# CareLite_1_21.net
KiCad netlist of a schematic drawn in Altium Designer
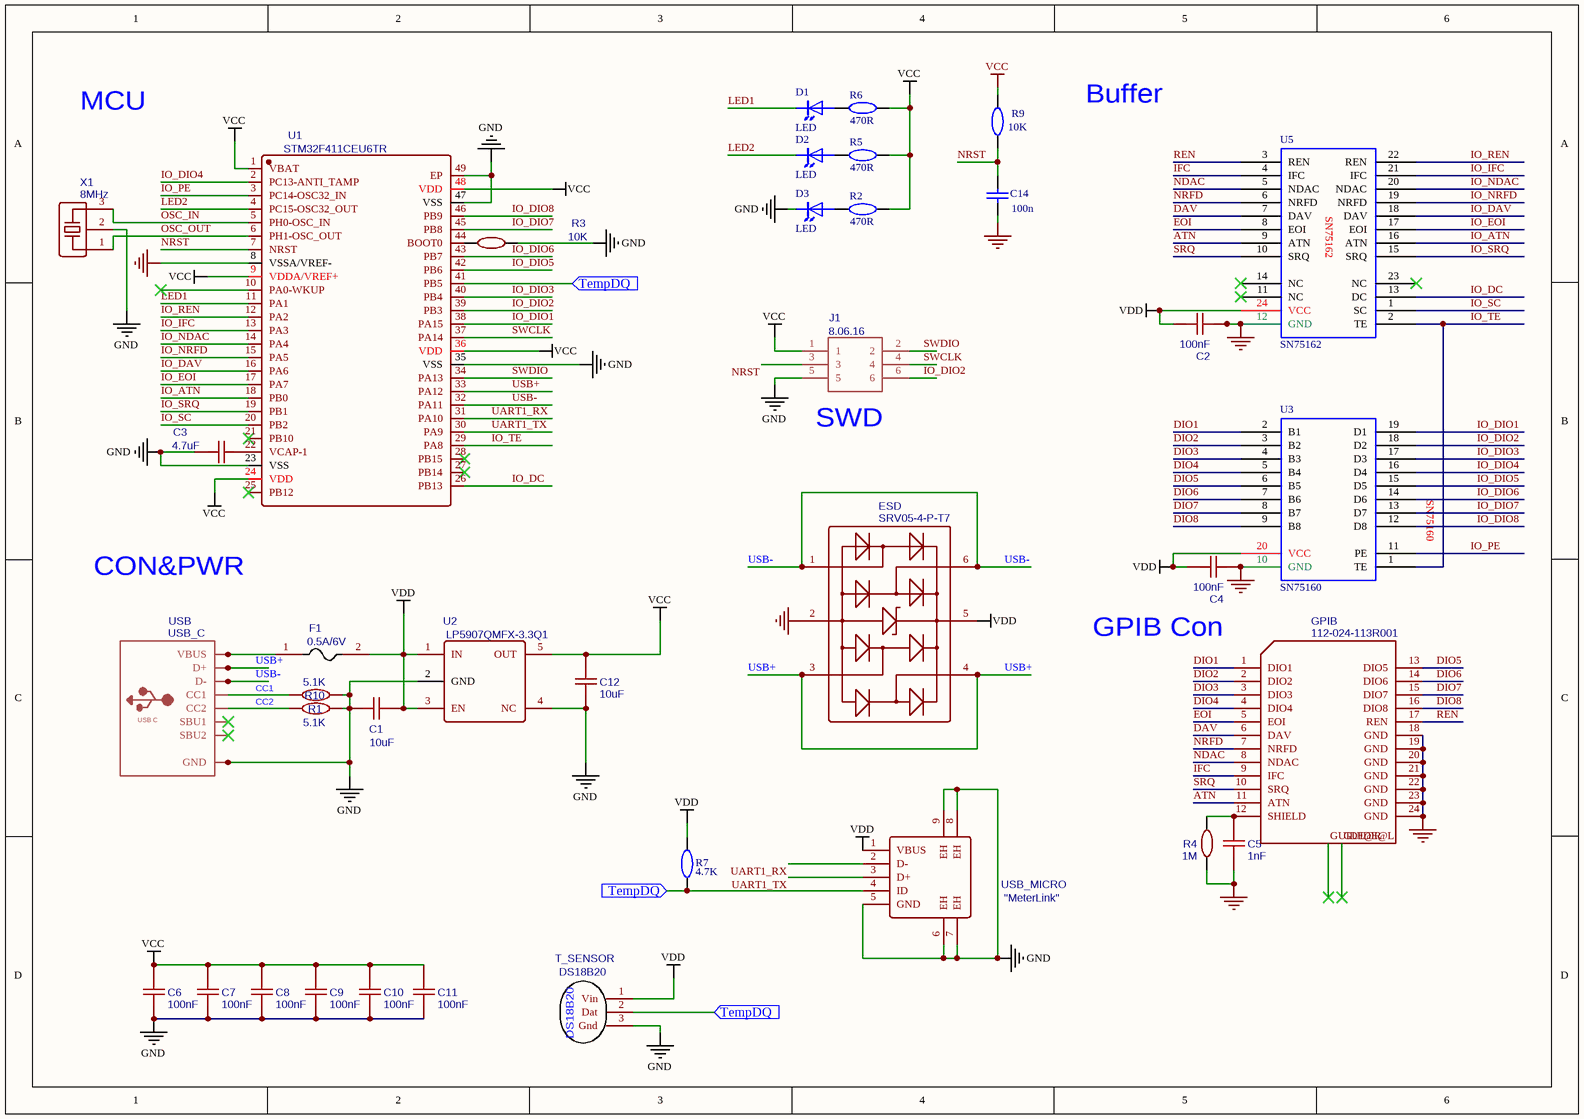
[diagram p0: CareLite 1.21.schdoc]

(export (version "E")
  (design (tool "Eeschema 10.0.6"))
  (components
    (comp (ref "C1")
      (value "10uF")
      (footprint "C0603")
      (fields
        (field (name "MANUFACTURER") "TAIYO YUDEN")
        (field (name "MANUFACTURER PART") "LMK107BJ106MALTD")
      )
      (libsource (lib "altium-import") (part "root_0_10uF_"))
    )
    (comp (ref "C2")
      (value "100nF")
      (footprint "C0603")
      (fields (field (name "MANUFACTURER") "YAGEO") (field (name "MANUFACTURER PART") "CC0402KRX7R7BB104"))
      (libsource (lib "altium-import") (part "root_2_100nF_"))
    )
    (comp (ref "C3")
      (value "4.7uF")
      (footprint "C0603")
      (fields
        (field (name "MANUFACTURER") "Huaxin S&T")
        (field (name "MANUFACTURER PART") "0603X475K160CT")
        (field (name "CONTRIBUTOR") "LCSC")
      )
      (libsource (lib "altium-import") (part "root_3_4.7uF_"))
    )
    (comp (ref "C4")
      (value "100nF")
      (footprint "C0603")
      (fields (field (name "MANUFACTURER") "YAGEO") (field (name "MANUFACTURER PART") "CC0402KRX7R7BB104"))
      (libsource (lib "altium-import") (part "root_2_100nF_"))
    )
    (comp (ref "C5")
      (value "1nF")
      (footprint "C0603")
      (fields
        (field (name "MANUFACTURER") "YAGEO")
        (field (name "MANUFACTURER PART") "CC0603KRX7RABB102")
        (field (name "CONTRIBUTOR") "LCSC")
      )
      (libsource (lib "altium-import") (part "root_0_1nF_"))
    )
    (comp (ref "C6")
      (value "100nF")
      (footprint "C0603")
      (fields (field (name "MANUFACTURER") "YAGEO") (field (name "MANUFACTURER PART") "CC0402KRX7R7BB104"))
      (libsource (lib "altium-import") (part "root_1_100nF_"))
    )
    (comp (ref "C7")
      (value "100nF")
      (footprint "C0603")
      (fields (field (name "MANUFACTURER") "YAGEO") (field (name "MANUFACTURER PART") "CC0402KRX7R7BB104"))
      (libsource (lib "altium-import") (part "root_1_100nF_"))
    )
    (comp (ref "C8")
      (value "100nF")
      (footprint "C0603")
      (fields (field (name "MANUFACTURER") "YAGEO") (field (name "MANUFACTURER PART") "CC0402KRX7R7BB104"))
      (libsource (lib "altium-import") (part "root_1_100nF_"))
    )
    (comp (ref "C9")
      (value "100nF")
      (footprint "C0603")
      (fields (field (name "MANUFACTURER") "YAGEO") (field (name "MANUFACTURER PART") "CC0402KRX7R7BB104"))
      (libsource (lib "altium-import") (part "root_1_100nF_"))
    )
    (comp (ref "C10")
      (value "100nF")
      (footprint "C0603")
      (fields (field (name "MANUFACTURER") "YAGEO") (field (name "MANUFACTURER PART") "CC0402KRX7R7BB104"))
      (libsource (lib "altium-import") (part "root_1_100nF_"))
    )
    (comp (ref "C11")
      (value "100nF")
      (footprint "C0603")
      (fields (field (name "MANUFACTURER") "YAGEO") (field (name "MANUFACTURER PART") "CC0402KRX7R7BB104"))
      (libsource (lib "altium-import") (part "root_1_100nF_"))
    )
    (comp (ref "C12")
      (value "10uF")
      (footprint "C0603")
      (fields
        (field (name "MANUFACTURER") "TAIYO YUDEN")
        (field (name "MANUFACTURER PART") "LMK107BJ106MALTD")
      )
      (libsource (lib "altium-import") (part "root_1_10uF_"))
    )
    (comp (ref "C14")
      (value "100n")
      (footprint "C0603")
      (fields (field (name "PUBLISHER") "Altium Limited"))
      (libsource (lib "altium-import") (part "root_1_100n_"))
    )
    (comp (ref "D1")
      (value "LED")
      (footprint "LED0603-FD")
      (libsource (lib "altium-import") (part "root_2_LED_"))
    )
    (comp (ref "D2")
      (value "LED")
      (footprint "LED0603-FD")
      (libsource (lib "altium-import") (part "root_2_LED_"))
    )
    (comp (ref "D3")
      (value "LED")
      (footprint "LED0603-FD")
      (libsource (lib "altium-import") (part "root_2_LED_"))
    )
    (comp (ref "ESD")
      (value "SRV05-4-P-T7")
      (footprint "SOT-23-6_L2.9-W1.6-P0.95-LS2.8-BL")
      (fields (field (name "MANUFACTURER") "PROTEK"))
      (libsource (lib "altium-import") (part "root_0_SRV05-4-P-T7_"))
    )
    (comp (ref "F1")
      (value "0.5A/6V")
      (footprint "0805_L_JX")
      (libsource (lib "altium-import") (part "root_0_0.5A/6V_"))
    )
    (comp (ref "GPIB")
      (value "112-024-113R001")
      (footprint "IEEE-488 SOCKET, 24PIN, RIGHT ANGLE, MALE, 112-024-113R001, FUY57109")
      (fields (field (name "MANUFACTURER") "norcomp") (field (name "CONTRIBUTOR") "misslee"))
      (libsource (lib "altium-import") (part "root_0_112-024-113R001_"))
    )
    (comp (ref "J1")
      (value "8.06.16")
      (footprint "80616-S")
      (fields (field (name "CONTRIBUTOR") "misslee"))
      (libsource (lib "altium-import") (part "root_0_8.06.16_"))
    )
    (comp (ref "R1")
      (value "5.1K")
      (footprint "R0603")
      (fields
        (field (name "MANUFACTURER") "Guangdong Fenghua Advanced Tech")
        (field (name "MANUFACTURER PART") "RS-03K5101FT")
        (field (name "CONTRIBUTOR") "LCSC")
      )
      (libsource (lib "altium-import") (part "root_0_5.1K_"))
    )
    (comp (ref "R2")
      (value "470R")
      (footprint "R0603")
      (fields (field (name "PUBLISHER") "Altium Limited"))
      (libsource (lib "altium-import") (part "root_2_470R_"))
    )
    (comp (ref "R3")
      (value "10K")
      (footprint "R0603")
      (fields (field (name "MANUFACTURER") "YAGEO") (field (name "MANUFACTURER PART") "RC0402FR-0710KL"))
      (libsource (lib "altium-import") (part "root_0_10K_"))
    )
    (comp (ref "R4")
      (value "1M")
      (footprint "R0603")
      (fields (field (name "MANUFACTURER") "YAGEO") (field (name "MANUFACTURER PART") "RC0603JR-071ML"))
      (libsource (lib "altium-import") (part "root_3_1M_"))
    )
    (comp (ref "R5")
      (value "470R")
      (footprint "R0603")
      (fields (field (name "PUBLISHER") "Altium Limited"))
      (libsource (lib "altium-import") (part "root_2_470R_"))
    )
    (comp (ref "R6")
      (value "470R")
      (footprint "R0603")
      (fields (field (name "PUBLISHER") "Altium Limited"))
      (libsource (lib "altium-import") (part "root_2_470R_"))
    )
    (comp (ref "R7")
      (value "4.7K")
      (footprint "R0603")
      (fields (field (name "PUBLISHER") "Altium Limited"))
      (libsource (lib "altium-import") (part "root_3_4.7K_"))
    )
    (comp (ref "R9")
      (value "10K")
      (footprint "R0603")
      (fields (field (name "PUBLISHER") "Altium Limited"))
      (libsource (lib "altium-import") (part "root_1_10K_"))
    )
    (comp (ref "R10")
      (value "5.1K")
      (footprint "R0603")
      (fields
        (field (name "MANUFACTURER") "Guangdong Fenghua Advanced Tech")
        (field (name "MANUFACTURER PART") "RS-03K5101FT")
        (field (name "CONTRIBUTOR") "LCSC")
      )
      (libsource (lib "altium-import") (part "root_0_5.1K_"))
    )
    (comp (ref "T_SENSOR")
      (value "DS18B20")
      (footprint "DS18B20")
      (fields (field (name "CONTRIBUTOR") "aleja_claros"))
      (libsource (lib "altium-import") (part "root_0_DS18B20_"))
    )
    (comp (ref "U1")
      (value "STM32F411CEU6TR")
      (footprint "QFN-48_L7.0-W7.0-P0.50-BL-EP5.1")
      (fields
        (field (name "MANUFACTURER") "STMicroelectronics")
        (field (name "MANUFACTURER PART") "STM32F411CCU6TR")
        (field (name "CONTRIBUTOR") "LCSC")
      )
      (libsource (lib "altium-import") (part "root_0_STM32F411CEU6TR_"))
    )
    (comp (ref "U2")
      (value "LP5907QMFX-3.3Q1")
      (footprint "SOT-23-5_L3.0-W1.7-P0.95-LS2.8-BR")
      (fields (field (name "MANUFACTURER") "TI") (field (name "CONTRIBUTOR") "LCSC"))
      (libsource (lib "altium-import") (part "root_0_LP5907QMFX-3.3Q1_"))
    )
    (comp (ref "U3")
      (value "SN75160")
      (footprint "SOIC127P1030-20AM")
      (libsource (lib "altium-import") (part "root_0_SN75160_"))
    )
    (comp (ref "U5")
      (value "SN75162")
      (footprint "SOIC127P1030-24AM")
      (libsource (lib "altium-import") (part "root_0_SN75162_"))
    )
    (comp (ref "USB")
      (value "USB_C")
      (footprint "USB_C_CUSB31-CFM2AX-01-Y")
      (fields (field (name "CONTRIBUTOR") "misslee"))
      (libsource (lib "altium-import") (part "root_0_USB_C_"))
    )
    (comp (ref "USB_MICRO")
      (value "\"MeterLink\"")
      (footprint "MIRCO-USB-SMD_U-D-M7DS-G-2")
      (fields
        (field (name "MANUFACTURER") "XKB Connectivity(中国星坤)")
        (field (name "MANUFACTURER PART") "U-D-M7DS-G-2")
        (field (name "CONTRIBUTOR") "LCSC")
      )
      (libsource (lib "altium-import") (part "root_0_{dblquote}MeterLink{dblquote}_"))
    )
    (comp (ref "X1")
      (value "8MHz")
      (footprint "OSC-SMD_3P-L3.2-W1.3-P1.2-L")
      (fields (field (name "MANUFACTURER PART") "CSTCE8M00G52-R0") (field (name "MANUFACTURER") "MuRata"))
      (libsource (lib "altium-import") (part "root_1_8MHz_"))
    )
  )
  (nets
    (net (code "1") (name "/ATN") (class "Default")
      (node (ref "GPIB") (pin "11") (pinfunction "ATN_11") (pintype "passive"))
      (node (ref "U5") (pin "9") (pinfunction "ATN_9") (pintype "passive"))
    )
    (net (code "2") (name "/CC1") (class "Default")
      (node (ref "R10") (pin "1") (pinfunction "1_1") (pintype "passive"))
      (node (ref "USB") (pin "A5") (pinfunction "CC1_A5") (pintype "passive"))
    )
    (net (code "3") (name "/CC2") (class "Default")
      (node (ref "R1") (pin "1") (pinfunction "1_1") (pintype "passive"))
      (node (ref "USB") (pin "B5") (pinfunction "CC2_B5") (pintype "passive"))
    )
    (net (code "4") (name "/DAV") (class "Default")
      (node (ref "GPIB") (pin "6") (pinfunction "DAV_6") (pintype "passive"))
      (node (ref "U5") (pin "7") (pinfunction "DAV_7") (pintype "passive"))
    )
    (net (code "5") (name "/DIO1") (class "Default")
      (node (ref "GPIB") (pin "1") (pinfunction "DIO1_1") (pintype "passive"))
      (node (ref "U3") (pin "2") (pinfunction "B1_2") (pintype "passive"))
    )
    (net (code "6") (name "/DIO2") (class "Default")
      (node (ref "GPIB") (pin "2") (pinfunction "DIO2_2") (pintype "passive"))
      (node (ref "U3") (pin "3") (pinfunction "B2_3") (pintype "passive"))
    )
    (net (code "7") (name "/DIO3") (class "Default")
      (node (ref "GPIB") (pin "3") (pinfunction "DIO3_3") (pintype "passive"))
      (node (ref "U3") (pin "4") (pinfunction "B3_4") (pintype "passive"))
    )
    (net (code "8") (name "/DIO4") (class "Default")
      (node (ref "GPIB") (pin "4") (pinfunction "DIO4_4") (pintype "passive"))
      (node (ref "U3") (pin "5") (pinfunction "B4_5") (pintype "passive"))
    )
    (net (code "9") (name "/DIO5") (class "Default")
      (node (ref "GPIB") (pin "13") (pinfunction "DIO5_13") (pintype "passive"))
      (node (ref "U3") (pin "6") (pinfunction "B5_6") (pintype "passive"))
    )
    (net (code "10") (name "/DIO6") (class "Default")
      (node (ref "GPIB") (pin "14") (pinfunction "DIO6_14") (pintype "passive"))
      (node (ref "U3") (pin "7") (pinfunction "B6_7") (pintype "passive"))
    )
    (net (code "11") (name "/DIO7") (class "Default")
      (node (ref "GPIB") (pin "15") (pinfunction "DIO7_15") (pintype "passive"))
      (node (ref "U3") (pin "8") (pinfunction "B7_8") (pintype "passive"))
    )
    (net (code "12") (name "/DIO8") (class "Default")
      (node (ref "GPIB") (pin "16") (pinfunction "DIO8_16") (pintype "passive"))
      (node (ref "U3") (pin "9") (pinfunction "B8_9") (pintype "passive"))
    )
    (net (code "13") (name "/EOI") (class "Default")
      (node (ref "GPIB") (pin "5") (pinfunction "EOI_5") (pintype "passive"))
      (node (ref "U5") (pin "8") (pinfunction "EOI_8") (pintype "passive"))
    )
    (net (code "14") (name "/IFC") (class "Default")
      (node (ref "GPIB") (pin "9") (pinfunction "IFC_9") (pintype "passive"))
      (node (ref "U5") (pin "4") (pinfunction "IFC_4") (pintype "passive"))
    )
    (net (code "15") (name "/IO_ATN") (class "Default")
      (node (ref "U1") (pin "18") (pinfunction "PB0_18") (pintype "passive"))
      (node (ref "U5") (pin "16") (pinfunction "ATN_16") (pintype "passive"))
    )
    (net (code "16") (name "/IO_DAV") (class "Default")
      (node (ref "U1") (pin "16") (pinfunction "PA6_16") (pintype "passive"))
      (node (ref "U5") (pin "18") (pinfunction "DAV_18") (pintype "passive"))
    )
    (net (code "17") (name "/IO_DC") (class "Default")
      (node (ref "U1") (pin "26") (pinfunction "PB13_26") (pintype "passive"))
      (node (ref "U5") (pin "13") (pinfunction "DC_13") (pintype "passive"))
    )
    (net (code "18") (name "/IO_DIO1") (class "Default")
      (node (ref "U1") (pin "38") (pinfunction "PA15_38") (pintype "passive"))
      (node (ref "U3") (pin "19") (pinfunction "D1_19") (pintype "passive"))
    )
    (net (code "19") (name "/IO_DIO2") (class "Default")
      (node (ref "J1") (pin "6") (pinfunction "6_6") (pintype "passive"))
      (node (ref "U1") (pin "39") (pinfunction "PB3_39") (pintype "passive"))
      (node (ref "U3") (pin "18") (pinfunction "D2_18") (pintype "passive"))
    )
    (net (code "20") (name "/IO_DIO3") (class "Default")
      (node (ref "U1") (pin "40") (pinfunction "PB4_40") (pintype "passive"))
      (node (ref "U3") (pin "17") (pinfunction "D3_17") (pintype "passive"))
    )
    (net (code "21") (name "/IO_DIO4") (class "Default")
      (node (ref "U1") (pin "2") (pinfunction "PC13-ANTI_TAMP_2") (pintype "passive"))
      (node (ref "U3") (pin "16") (pinfunction "D4_16") (pintype "passive"))
    )
    (net (code "22") (name "/IO_DIO5") (class "Default")
      (node (ref "U1") (pin "42") (pinfunction "PB6_42") (pintype "passive"))
      (node (ref "U3") (pin "15") (pinfunction "D5_15") (pintype "passive"))
    )
    (net (code "23") (name "/IO_DIO6") (class "Default")
      (node (ref "U1") (pin "43") (pinfunction "PB7_43") (pintype "passive"))
      (node (ref "U3") (pin "14") (pinfunction "D6_14") (pintype "passive"))
    )
    (net (code "24") (name "/IO_DIO7") (class "Default")
      (node (ref "U1") (pin "45") (pinfunction "PB8_45") (pintype "passive"))
      (node (ref "U3") (pin "13") (pinfunction "D7_13") (pintype "passive"))
    )
    (net (code "25") (name "/IO_DIO8") (class "Default")
      (node (ref "U1") (pin "46") (pinfunction "PB9_46") (pintype "passive"))
      (node (ref "U3") (pin "12") (pinfunction "D8_12") (pintype "passive"))
    )
    (net (code "26") (name "/IO_EOI") (class "Default")
      (node (ref "U1") (pin "17") (pinfunction "PA7_17") (pintype "passive"))
      (node (ref "U5") (pin "17") (pinfunction "EOI_17") (pintype "passive"))
    )
    (net (code "27") (name "/IO_IFC") (class "Default")
      (node (ref "U1") (pin "13") (pinfunction "PA3_13") (pintype "passive"))
      (node (ref "U5") (pin "21") (pinfunction "IFC_21") (pintype "passive"))
    )
    (net (code "28") (name "/IO_NDAC") (class "Default")
      (node (ref "U1") (pin "14") (pinfunction "PA4_14") (pintype "passive"))
      (node (ref "U5") (pin "20") (pinfunction "NDAC_20") (pintype "passive"))
    )
    (net (code "29") (name "/IO_NRFD") (class "Default")
      (node (ref "U1") (pin "15") (pinfunction "PA5_15") (pintype "passive"))
      (node (ref "U5") (pin "19") (pinfunction "NRFD_19") (pintype "passive"))
    )
    (net (code "30") (name "/IO_PE") (class "Default")
      (node (ref "U1") (pin "3") (pinfunction "PC14-OSC32_IN_3") (pintype "passive"))
      (node (ref "U3") (pin "11") (pinfunction "PE_11") (pintype "passive"))
    )
    (net (code "31") (name "/IO_REN") (class "Default")
      (node (ref "U1") (pin "12") (pinfunction "PA2_12") (pintype "passive"))
      (node (ref "U5") (pin "22") (pinfunction "REN_22") (pintype "passive"))
    )
    (net (code "32") (name "/IO_SC") (class "Default")
      (node (ref "U1") (pin "20") (pinfunction "PB2_20") (pintype "passive"))
      (node (ref "U5") (pin "1") (pinfunction "SC_1") (pintype "passive"))
    )
    (net (code "33") (name "/IO_SRQ") (class "Default")
      (node (ref "U1") (pin "19") (pinfunction "PB1_19") (pintype "passive"))
      (node (ref "U5") (pin "15") (pinfunction "SRQ_15") (pintype "passive"))
    )
    (net (code "34") (name "/IO_TE") (class "Default")
      (node (ref "U1") (pin "29") (pinfunction "PA8_29") (pintype "passive"))
      (node (ref "U3") (pin "1") (pinfunction "TE_1") (pintype "passive"))
      (node (ref "U5") (pin "2") (pinfunction "TE_2") (pintype "passive"))
    )
    (net (code "35") (name "/LED1") (class "Default")
      (node (ref "D1") (pin "2") (pinfunction "2_2") (pintype "passive"))
      (node (ref "U1") (pin "11") (pinfunction "PA1_11") (pintype "passive"))
    )
    (net (code "36") (name "/LED2") (class "Default")
      (node (ref "D2") (pin "2") (pinfunction "2_2") (pintype "passive"))
      (node (ref "U1") (pin "4") (pinfunction "PC15-OSC32_OUT_4") (pintype "passive"))
    )
    (net (code "37") (name "/NDAC") (class "Default")
      (node (ref "GPIB") (pin "8") (pinfunction "NDAC_8") (pintype "passive"))
      (node (ref "U5") (pin "5") (pinfunction "NDAC_5") (pintype "passive"))
    )
    (net (code "38") (name "/NRFD") (class "Default")
      (node (ref "GPIB") (pin "7") (pinfunction "NRFD_7") (pintype "passive"))
      (node (ref "U5") (pin "6") (pinfunction "NRFD_6") (pintype "passive"))
    )
    (net (code "39") (name "/NRST") (class "Default")
      (node (ref "C14") (pin "2") (pinfunction "2_2") (pintype "passive"))
      (node (ref "J1") (pin "3") (pinfunction "3_3") (pintype "passive"))
      (node (ref "R9") (pin "1") (pinfunction "1_1") (pintype "passive"))
      (node (ref "U1") (pin "7") (pinfunction "NRST_7") (pintype "passive"))
    )
    (net (code "40") (name "/OSC_IN") (class "Default")
      (node (ref "U1") (pin "5") (pinfunction "PH0-OSC_IN_5") (pintype "passive"))
      (node (ref "X1") (pin "3") (pinfunction "3_3") (pintype "passive"))
    )
    (net (code "41") (name "/OSC_OUT") (class "Default")
      (node (ref "U1") (pin "6") (pinfunction "PH1-OSC_OUT_6") (pintype "passive"))
      (node (ref "X1") (pin "1") (pinfunction "1_1") (pintype "passive"))
    )
    (net (code "42") (name "/REN") (class "Default")
      (node (ref "GPIB") (pin "17") (pinfunction "REN_17") (pintype "passive"))
      (node (ref "U5") (pin "3") (pinfunction "REN_3") (pintype "passive"))
    )
    (net (code "43") (name "/SRQ") (class "Default")
      (node (ref "GPIB") (pin "10") (pinfunction "SRQ_10") (pintype "passive"))
      (node (ref "U5") (pin "10") (pinfunction "SRQ_10") (pintype "passive"))
    )
    (net (code "44") (name "/SWCLK") (class "Default")
      (node (ref "J1") (pin "4") (pinfunction "4_4") (pintype "passive"))
      (node (ref "U1") (pin "37") (pinfunction "PA14_37") (pintype "passive"))
    )
    (net (code "45") (name "/SWDIO") (class "Default")
      (node (ref "J1") (pin "2") (pinfunction "2_2") (pintype "passive"))
      (node (ref "U1") (pin "34") (pinfunction "PA13_34") (pintype "passive"))
    )
    (net (code "46") (name "/TempDQ") (class "Default")
      (node (ref "R7") (pin "2") (pinfunction "2_2") (pintype "passive"))
      (node (ref "T_SENSOR") (pin "2") (pinfunction "Dat_2") (pintype "passive"))
      (node (ref "U1") (pin "41") (pinfunction "PB5_41") (pintype "passive"))
      (node (ref "USB_MICRO") (pin "4") (pinfunction "ID_4") (pintype "passive"))
    )
    (net (code "47") (name "/UART1_RX") (class "Default")
      (node (ref "U1") (pin "31") (pinfunction "PA10_31") (pintype "passive"))
      (node (ref "USB_MICRO") (pin "2") (pinfunction "D-_2") (pintype "passive"))
    )
    (net (code "48") (name "/UART1_TX") (class "Default")
      (node (ref "U1") (pin "30") (pinfunction "PA9_30") (pintype "passive"))
      (node (ref "USB_MICRO") (pin "3") (pinfunction "D+_3") (pintype "passive"))
    )
    (net (code "49") (name "/USB+") (class "Default")
      (node (ref "ESD") (pin "3") (pinfunction "3_3") (pintype "passive"))
      (node (ref "ESD") (pin "4") (pinfunction "4_4") (pintype "passive"))
      (node (ref "U1") (pin "33") (pinfunction "PA12_33") (pintype "passive"))
      (node (ref "USB") (pin "A6") (pinfunction "D+_A6") (pintype "passive"))
      (node (ref "USB") (pin "B6") (pinfunction "D+_B6") (pintype "passive"))
    )
    (net (code "50") (name "/USB-") (class "Default")
      (node (ref "ESD") (pin "1") (pinfunction "1_1") (pintype "passive"))
      (node (ref "ESD") (pin "6") (pinfunction "6_6") (pintype "passive"))
      (node (ref "U1") (pin "32") (pinfunction "PA11_32") (pintype "passive"))
      (node (ref "USB") (pin "A7") (pinfunction "D-_A7") (pintype "passive"))
      (node (ref "USB") (pin "B7") (pinfunction "D-_B7") (pintype "passive"))
    )
    (net (code "51") (name "GND") (class "Default")
      (node (ref "C1") (pin "1") (pinfunction "1_1") (pintype "passive"))
      (node (ref "C10") (pin "1") (pinfunction "1_1") (pintype "passive"))
      (node (ref "C11") (pin "1") (pinfunction "1_1") (pintype "passive"))
      (node (ref "C12") (pin "1") (pinfunction "1_1") (pintype "passive"))
      (node (ref "C14") (pin "1") (pinfunction "1_1") (pintype "passive"))
      (node (ref "C2") (pin "2") (pinfunction "2_2") (pintype "passive"))
      (node (ref "C3") (pin "1") (pinfunction "1_1") (pintype "passive"))
      (node (ref "C4") (pin "2") (pinfunction "2_2") (pintype "passive"))
      (node (ref "C5") (pin "1") (pinfunction "1_1") (pintype "passive"))
      (node (ref "C6") (pin "1") (pinfunction "1_1") (pintype "passive"))
      (node (ref "C7") (pin "1") (pinfunction "1_1") (pintype "passive"))
      (node (ref "C8") (pin "1") (pinfunction "1_1") (pintype "passive"))
      (node (ref "C9") (pin "1") (pinfunction "1_1") (pintype "passive"))
      (node (ref "D3") (pin "2") (pinfunction "2_2") (pintype "passive"))
      (node (ref "ESD") (pin "2") (pinfunction "2_2") (pintype "passive"))
      (node (ref "GPIB") (pin "18") (pinfunction "GND_18") (pintype "passive"))
      (node (ref "GPIB") (pin "19") (pinfunction "GND_19") (pintype "passive"))
      (node (ref "GPIB") (pin "20") (pinfunction "GND_20") (pintype "passive"))
      (node (ref "GPIB") (pin "21") (pinfunction "GND_21") (pintype "passive"))
      (node (ref "GPIB") (pin "22") (pinfunction "GND_22") (pintype "passive"))
      (node (ref "GPIB") (pin "23") (pinfunction "GND_23") (pintype "passive"))
      (node (ref "GPIB") (pin "24") (pinfunction "GND_24") (pintype "passive"))
      (node (ref "J1") (pin "5") (pinfunction "5_5") (pintype "passive"))
      (node (ref "R1") (pin "2") (pinfunction "2_2") (pintype "passive"))
      (node (ref "R10") (pin "2") (pinfunction "2_2") (pintype "passive"))
      (node (ref "R3") (pin "2") (pinfunction "2_2") (pintype "passive"))
      (node (ref "R4") (pin "2") (pinfunction "2_2") (pintype "passive"))
      (node (ref "T_SENSOR") (pin "3") (pinfunction "Gnd_3") (pintype "passive"))
      (node (ref "U1") (pin "23") (pinfunction "VSS_23") (pintype "passive"))
      (node (ref "U1") (pin "35") (pinfunction "VSS_35") (pintype "passive"))
      (node (ref "U1") (pin "47") (pinfunction "VSS_47") (pintype "passive"))
      (node (ref "U1") (pin "49") (pinfunction "EP_49") (pintype "passive"))
      (node (ref "U1") (pin "8") (pinfunction "VSSA/VREF-_8") (pintype "passive"))
      (node (ref "U2") (pin "2") (pinfunction "GND_2") (pintype "passive"))
      (node (ref "U2") (pin "4") (pinfunction "NC_4") (pintype "passive"))
      (node (ref "U3") (pin "10") (pinfunction "GND_10") (pintype "passive"))
      (node (ref "U5") (pin "12") (pinfunction "GND_12") (pintype "passive"))
      (node (ref "USB") (pin "A1B12") (pinfunction "GND_A1B12") (pintype "passive"))
      (node (ref "USB") (pin "B1A12") (pinfunction "GND_B1A12") (pintype "passive"))
      (node (ref "USB_MICRO") (pin "5") (pinfunction "GND_5") (pintype "passive"))
      (node (ref "USB_MICRO") (pin "6") (pinfunction "EH_6") (pintype "passive"))
      (node (ref "USB_MICRO") (pin "7") (pinfunction "EH_7") (pintype "passive"))
      (node (ref "USB_MICRO") (pin "8") (pinfunction "EH_8") (pintype "passive"))
      (node (ref "USB_MICRO") (pin "9") (pinfunction "EH_9") (pintype "passive"))
      (node (ref "X1") (pin "2") (pinfunction "2_2") (pintype "passive"))
    )
    (net (code "52") (name "Net-(D1-Pad1)") (class "Default")
      (node (ref "D1") (pin "1") (pinfunction "1_1") (pintype "passive"))
      (node (ref "R6") (pin "2") (pinfunction "2_2") (pintype "passive"))
    )
    (net (code "53") (name "Net-(D2-Pad1)") (class "Default")
      (node (ref "D2") (pin "1") (pinfunction "1_1") (pintype "passive"))
      (node (ref "R5") (pin "2") (pinfunction "2_2") (pintype "passive"))
    )
    (net (code "54") (name "Net-(D3-Pad1)") (class "Default")
      (node (ref "D3") (pin "1") (pinfunction "1_1") (pintype "passive"))
      (node (ref "R2") (pin "2") (pinfunction "2_2") (pintype "passive"))
    )
    (net (code "55") (name "Net-(F1-Pad1)") (class "Default")
      (node (ref "F1") (pin "1") (pinfunction "1_1") (pintype "passive"))
      (node (ref "USB") (pin "A4B9") (pinfunction "VBUS_A4B9") (pintype "passive"))
      (node (ref "USB") (pin "B4A9") (pinfunction "VBUS_B4A9") (pintype "passive"))
    )
    (net (code "56") (name "Net-(GPIB-SHIELD)") (class "Default")
      (node (ref "C5") (pin "2") (pinfunction "2_2") (pintype "passive"))
      (node (ref "GPIB") (pin "12") (pinfunction "SHIELD_12") (pintype "passive"))
      (node (ref "R4") (pin "1") (pinfunction "1_1") (pintype "passive"))
    )
    (net (code "57") (name "Net-(U1-BOOT0)") (class "Default")
      (node (ref "R3") (pin "1") (pinfunction "1_1") (pintype "passive"))
      (node (ref "U1") (pin "44") (pinfunction "BOOT0_44") (pintype "passive"))
    )
    (net (code "58") (name "Net-(U1-VCAP-1)") (class "Default")
      (node (ref "C3") (pin "2") (pinfunction "2_2") (pintype "passive"))
      (node (ref "U1") (pin "22") (pinfunction "VCAP-1_22") (pintype "passive"))
    )
    (net (code "59") (name "VCC") (class "Default")
      (node (ref "C10") (pin "2") (pinfunction "2_2") (pintype "passive"))
      (node (ref "C11") (pin "2") (pinfunction "2_2") (pintype "passive"))
      (node (ref "C12") (pin "2") (pinfunction "2_2") (pintype "passive"))
      (node (ref "C6") (pin "2") (pinfunction "2_2") (pintype "passive"))
      (node (ref "C7") (pin "2") (pinfunction "2_2") (pintype "passive"))
      (node (ref "C8") (pin "2") (pinfunction "2_2") (pintype "passive"))
      (node (ref "C9") (pin "2") (pinfunction "2_2") (pintype "passive"))
      (node (ref "J1") (pin "1") (pinfunction "1_1") (pintype "passive"))
      (node (ref "R2") (pin "1") (pinfunction "1_1") (pintype "passive"))
      (node (ref "R5") (pin "1") (pinfunction "1_1") (pintype "passive"))
      (node (ref "R6") (pin "1") (pinfunction "1_1") (pintype "passive"))
      (node (ref "R9") (pin "2") (pinfunction "2_2") (pintype "passive"))
      (node (ref "U1") (pin "1") (pinfunction "VBAT_1") (pintype "passive"))
      (node (ref "U1") (pin "24") (pinfunction "VDD_24") (pintype "passive"))
      (node (ref "U1") (pin "36") (pinfunction "VDD_36") (pintype "passive"))
      (node (ref "U1") (pin "48") (pinfunction "VDD_48") (pintype "passive"))
      (node (ref "U1") (pin "9") (pinfunction "VDDA/VREF+_9") (pintype "passive"))
      (node (ref "U2") (pin "5") (pinfunction "OUT_5") (pintype "passive"))
    )
    (net (code "60") (name "VDD") (class "Default")
      (node (ref "C1") (pin "2") (pinfunction "2_2") (pintype "passive"))
      (node (ref "C2") (pin "1") (pinfunction "1_1") (pintype "passive"))
      (node (ref "C4") (pin "1") (pinfunction "1_1") (pintype "passive"))
      (node (ref "ESD") (pin "5") (pinfunction "5_5") (pintype "passive"))
      (node (ref "F1") (pin "2") (pinfunction "2_2") (pintype "passive"))
      (node (ref "R7") (pin "1") (pinfunction "1_1") (pintype "passive"))
      (node (ref "T_SENSOR") (pin "1") (pinfunction "Vin_1") (pintype "passive"))
      (node (ref "U2") (pin "1") (pinfunction "IN_1") (pintype "passive"))
      (node (ref "U2") (pin "3") (pinfunction "EN_3") (pintype "passive"))
      (node (ref "U3") (pin "20") (pinfunction "VCC_20") (pintype "passive"))
      (node (ref "U5") (pin "24") (pinfunction "VCC_24") (pintype "passive"))
      (node (ref "USB_MICRO") (pin "1") (pinfunction "VBUS_1") (pintype "passive"))
    )
    (net (code "61") (name "unconnected-(GPIB-P$25-PadGUIDE@L)") (class "Default")
      (node (ref "GPIB") (pin "GUIDE@L") (pinfunction "P$25_GUIDE@L") (pintype "passive+no_connect"))
    )
    (net (code "62") (name "unconnected-(GPIB-P$26-PadGUIDE@R)") (class "Default")
      (node (ref "GPIB") (pin "GUIDE@R") (pinfunction "P$26_GUIDE@R") (pintype "passive+no_connect"))
    )
    (net (code "63") (name "unconnected-(U1-PA0-WKUP-Pad10)") (class "Default")
      (node (ref "U1") (pin "10") (pinfunction "PA0-WKUP_10") (pintype "passive+no_connect"))
    )
    (net (code "64") (name "unconnected-(U1-PB10-Pad21)") (class "Default")
      (node (ref "U1") (pin "21") (pinfunction "PB10_21") (pintype "passive+no_connect"))
    )
    (net (code "65") (name "unconnected-(U1-PB12-Pad25)") (class "Default")
      (node (ref "U1") (pin "25") (pinfunction "PB12_25") (pintype "passive+no_connect"))
    )
    (net (code "66") (name "unconnected-(U1-PB14-Pad27)") (class "Default")
      (node (ref "U1") (pin "27") (pinfunction "PB14_27") (pintype "passive+no_connect"))
    )
    (net (code "67") (name "unconnected-(U1-PB15-Pad28)") (class "Default")
      (node (ref "U1") (pin "28") (pinfunction "PB15_28") (pintype "passive+no_connect"))
    )
    (net (code "68") (name "unconnected-(U5-NC-Pad11)") (class "Default")
      (node (ref "U5") (pin "11") (pinfunction "NC_11") (pintype "passive+no_connect"))
    )
    (net (code "69") (name "unconnected-(U5-NC-Pad14)") (class "Default")
      (node (ref "U5") (pin "14") (pinfunction "NC_14") (pintype "passive+no_connect"))
    )
    (net (code "70") (name "unconnected-(U5-NC-Pad23)") (class "Default")
      (node (ref "U5") (pin "23") (pinfunction "NC_23") (pintype "passive+no_connect"))
    )
    (net (code "71") (name "unconnected-(USB-SBU1-PadA8)") (class "Default")
      (node (ref "USB") (pin "A8") (pinfunction "SBU1_A8") (pintype "passive+no_connect"))
    )
    (net (code "72") (name "unconnected-(USB-SBU2-PadB8)") (class "Default")
      (node (ref "USB") (pin "B8") (pinfunction "SBU2_B8") (pintype "passive+no_connect"))
    )
  )
)
